# AltimeterFio_v3.net
KiCad netlist of a schematic drawn in EAGLE
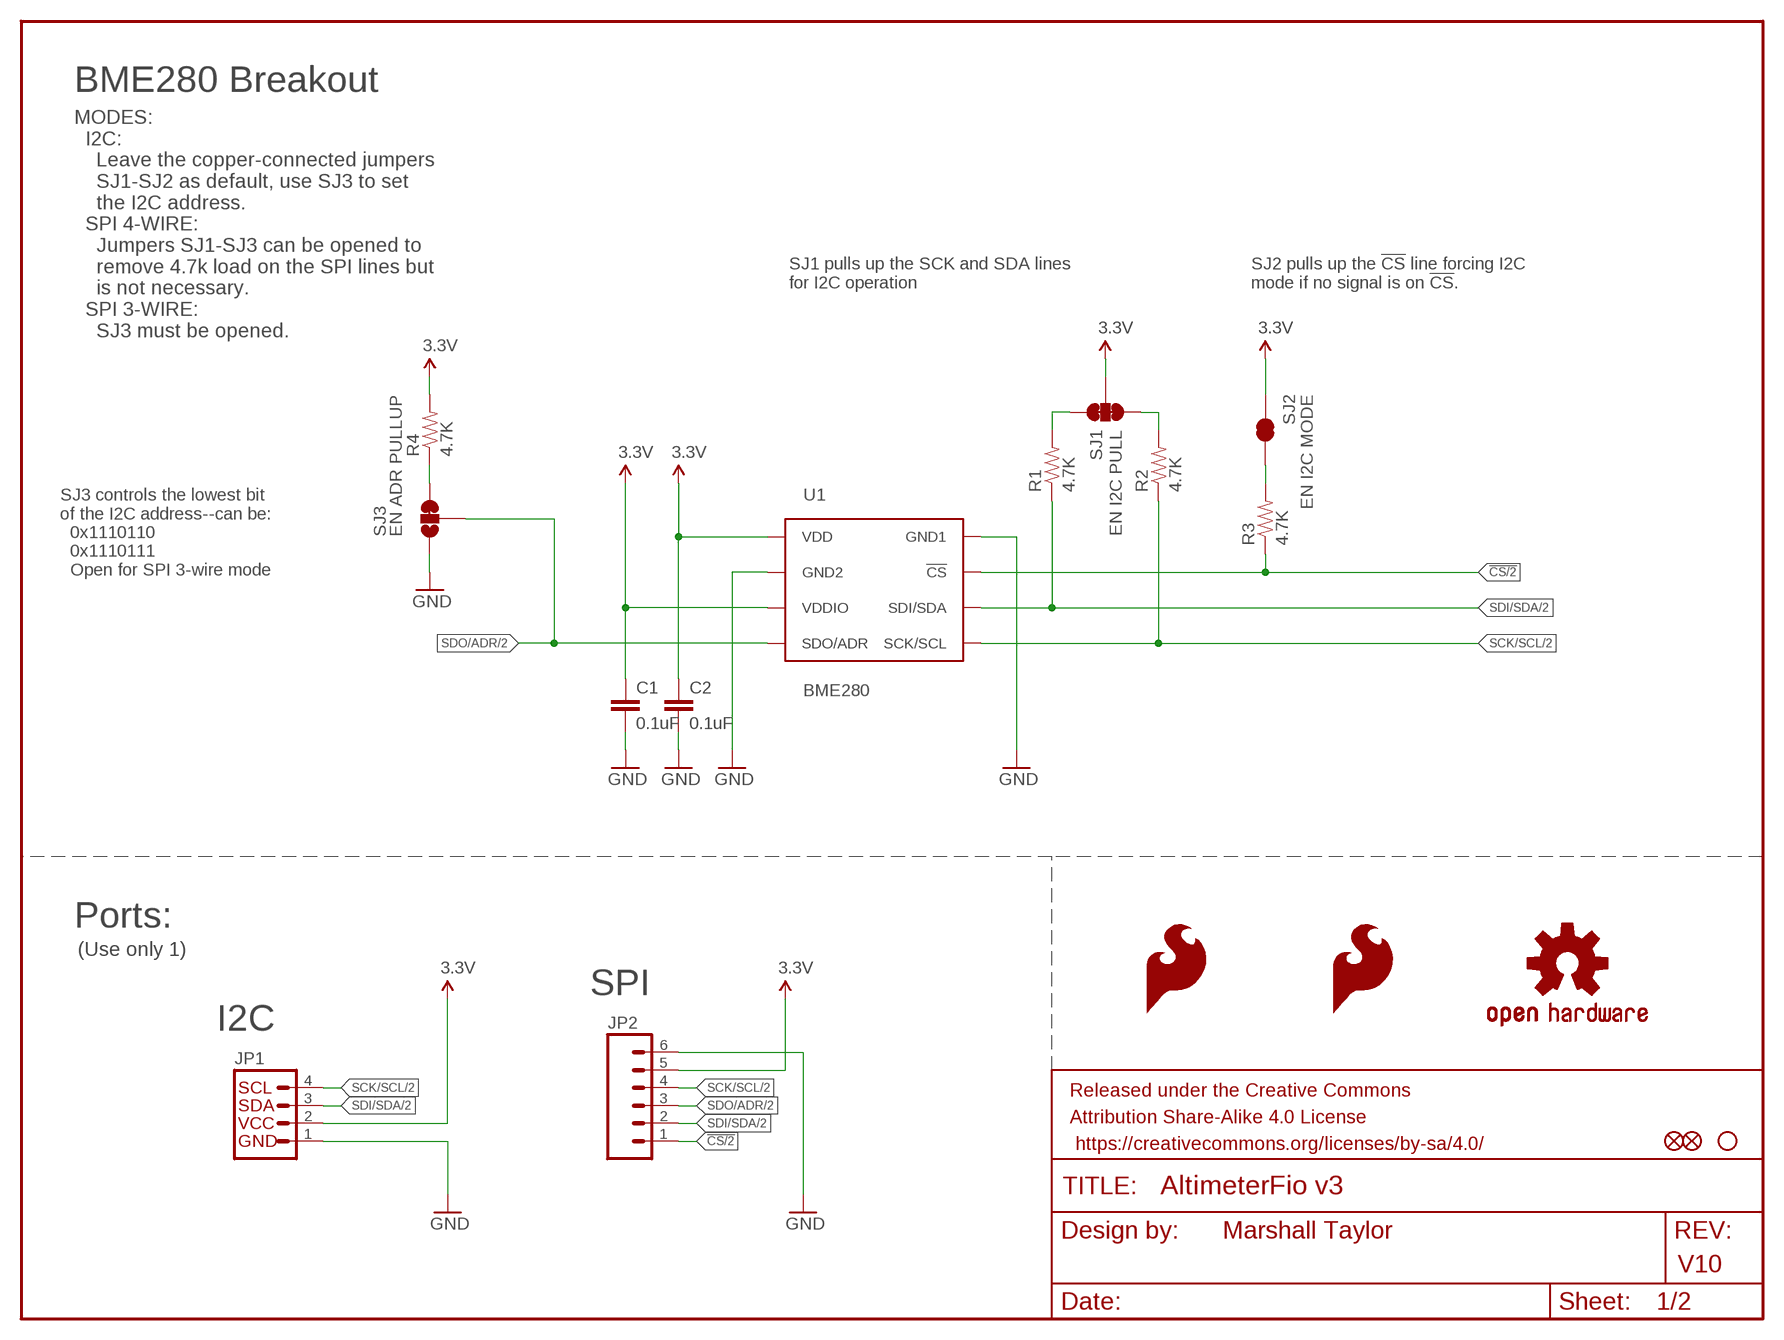
[diagram p0: schematic, sheet 1]
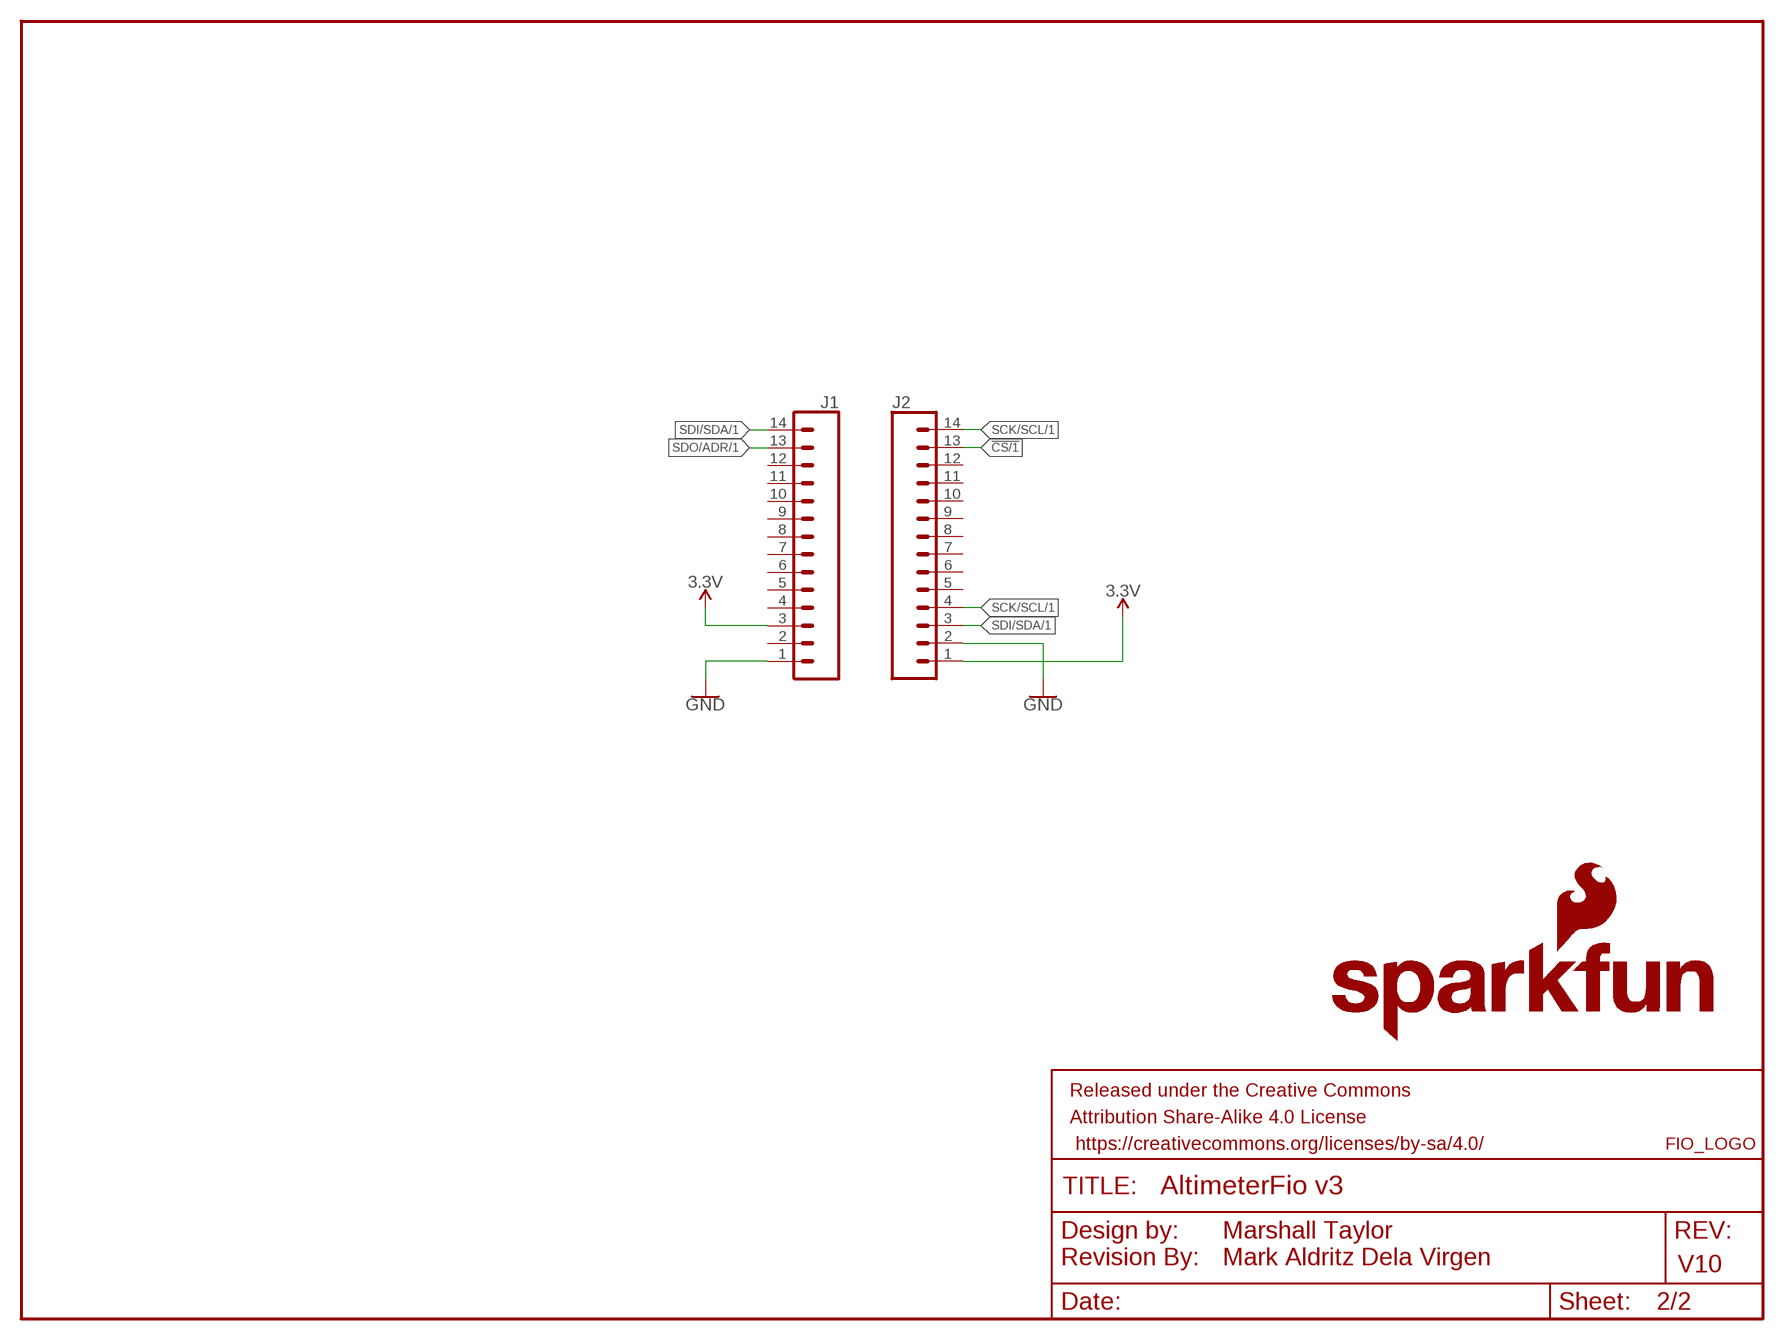
[diagram p1: schematic, sheet 2]

(export (version "E")
  (design (tool "Eeschema 10.0.6"))
  (components
    (comp (ref "FRAME2")
      (value "FRAME-LETTERNO_PACKAGE")
      (footprint "eagle-import:DUMMY")
      (fields (field (name "DESIGNER") "Nobody"))
      (libsource (lib "eagle-import") (part "SparkFun-Aesthetics_507_FRAME-LETTERNO_PACKAGE"))
    )
    (comp (ref "J1")
      (value "CONN_14")
      (footprint "eagle-import:1X14")
      (libsource (lib "eagle-import") (part "CONN_14"))
    )
    (comp (ref "J2")
      (value "CONN_14")
      (footprint "eagle-import:1X14")
      (libsource (lib "eagle-import") (part "CONN_14"))
    )
    (comp (ref "LOGO4")
      (value "FIO_LOGOV2")
      (footprint "eagle-import:FIO_LOGO")
      (libsource (lib "eagle-import") (part "FIO_LOGOV2"))
    )
    (comp (ref "LOGO5")
      (value "REVISION")
      (footprint "eagle-import:REVISION")
      (libsource (lib "eagle-import") (part "REVISION"))
    )
    (comp (ref "LOGO6")
      (value "SFE_LOGO_NAME_FLAME.1_INCH")
      (footprint "eagle-import:SFE_LOGO_NAME_FLAME_.1")
      (libsource (lib "eagle-import") (part "SFE_LOGO_NAME_FLAME.1_INCH"))
    )
    (comp (ref "C1")
      (value "0.1uF")
      (footprint "eagle-import:0603-CAP")
      (libsource (lib "eagle-import") (part "0.1UF-25V-5%(0603)"))
    )
    (comp (ref "C2")
      (value "0.1uF")
      (footprint "eagle-import:0603-CAP")
      (libsource (lib "eagle-import") (part "0.1UF-25V-5%(0603)"))
    )
    (comp (ref "FID1")
      (value "FIDUCIAL1X2")
      (footprint "eagle-import:FIDUCIAL-1X2")
      (libsource (lib "eagle-import") (part "FIDUCIAL1X2"))
    )
    (comp (ref "FID2")
      (value "FIDUCIAL1X2")
      (footprint "eagle-import:FIDUCIAL-1X2")
      (libsource (lib "eagle-import") (part "FIDUCIAL1X2"))
    )
    (comp (ref "FRAME1")
      (value "FRAME-LETTER")
      (footprint "eagle-import:CREATIVE_COMMONS")
      (libsource (lib "eagle-import") (part "FRAME-LETTER"))
    )
    (comp (ref "JP1")
      (value "I2C_STANDARD_NO_SILK")
      (footprint "eagle-import:1X04_NO_SILK")
      (libsource (lib "eagle-import") (part "I2C_STANDARD_NO_SILK"))
    )
    (comp (ref "JP2")
      (value "M06NO_SILK_FEMALE_PTH")
      (footprint "eagle-import:1X06_NO_SILK")
      (libsource (lib "eagle-import") (part "M06NO_SILK_FEMALE_PTH"))
    )
    (comp (ref "LOGO1")
      (value "SFE_LOGO_FLAME.1_INCH")
      (footprint "eagle-import:SFE_LOGO_FLAME_.1")
      (libsource (lib "eagle-import") (part "SFE_LOGO_FLAME.1_INCH"))
    )
    (comp (ref "LOGO2")
      (value "SFE_LOGO_FLAME.1_INCH")
      (footprint "eagle-import:SFE_LOGO_FLAME_.1")
      (libsource (lib "eagle-import") (part "SFE_LOGO_FLAME.1_INCH"))
    )
    (comp (ref "LOGO3")
      (value "OSHW-LOGOS")
      (footprint "eagle-import:OSHW-LOGO-S")
      (libsource (lib "eagle-import") (part "OSHW-LOGOS"))
    )
    (comp (ref "R1")
      (value "4.7K")
      (footprint "eagle-import:0603-RES")
      (libsource (lib "eagle-import") (part "4.7KOHM-1/10W-1%(0603)"))
    )
    (comp (ref "R2")
      (value "4.7K")
      (footprint "eagle-import:0603-RES")
      (libsource (lib "eagle-import") (part "4.7KOHM-1/10W-1%(0603)"))
    )
    (comp (ref "R3")
      (value "4.7K")
      (footprint "eagle-import:0603-RES")
      (libsource (lib "eagle-import") (part "4.7KOHM-1/10W-1%(0603)"))
    )
    (comp (ref "R4")
      (value "4.7K")
      (footprint "eagle-import:0603-RES")
      (libsource (lib "eagle-import") (part "4.7KOHM-1/10W-1%(0603)"))
    )
    (comp (ref "SJ1")
      (value "EN I2C PULL")
      (footprint "eagle-import:PAD-JUMPER-3-3OF3_NC_BY_TRACE_YES_SILK_FULL_BOX")
      (libsource (lib "eagle-import") (part "JUMPER-PAD-3-NC_BY_TRACE"))
    )
    (comp (ref "SJ2")
      (value "EN I2C MODE")
      (footprint "eagle-import:PAD-JUMPER-2-NC_BY_TRACE_YES_SILK")
      (libsource (lib "eagle-import") (part "JUMPER-PAD-2-NC_BY_TRACE"))
    )
    (comp (ref "SJ3")
      (value "EN ADR PULLUP")
      (footprint "eagle-import:PAD-JUMPER-3-2OF3_NC_BY_TRACE_YES_SILK_FULL_BOX")
      (libsource (lib "eagle-import") (part "JUMPER-PAD-3-2OF3_NC_BY_TRACE_SMALL"))
    )
    (comp (ref "STANDOFF4")
      (value "STAND-OFF")
      (footprint "eagle-import:STAND-OFF")
      (libsource (lib "eagle-import") (part "STAND-OFF"))
    )
    (comp (ref "U1")
      (value "BME280")
      (footprint "eagle-import:BME280_LGA")
      (libsource (lib "eagle-import") (part "BME280"))
    )
  )
  (nets
    (net (code "1") (name "3.3V") (class "Default")
      (node (ref "C1") (pin "1") (pinfunction "1_1") (pintype "passive"))
      (node (ref "C2") (pin "1") (pinfunction "1_1") (pintype "passive"))
      (node (ref "J1") (pin "3") (pinfunction "3_3") (pintype "passive"))
      (node (ref "J2") (pin "1") (pinfunction "1_1") (pintype "passive"))
      (node (ref "JP1") (pin "2") (pinfunction "2_2") (pintype "passive"))
      (node (ref "JP2") (pin "5") (pinfunction "5_5") (pintype "passive"))
      (node (ref "R4") (pin "2") (pinfunction "2_2") (pintype "passive"))
      (node (ref "SJ1") (pin "2") (pinfunction "2_2") (pintype "passive"))
      (node (ref "SJ2") (pin "2") (pinfunction "2_2") (pintype "passive"))
      (node (ref "U1") (pin "P$6") (pinfunction "VDDIO_P$6") (pintype "bidirectional"))
      (node (ref "U1") (pin "P$8") (pinfunction "VDD_P$8") (pintype "bidirectional"))
    )
    (net (code "2") (name "GND") (class "Default")
      (node (ref "C1") (pin "2") (pinfunction "2_2") (pintype "passive"))
      (node (ref "C2") (pin "2") (pinfunction "2_2") (pintype "passive"))
      (node (ref "J1") (pin "1") (pinfunction "1_1") (pintype "passive"))
      (node (ref "J2") (pin "2") (pinfunction "2_2") (pintype "passive"))
      (node (ref "JP1") (pin "1") (pinfunction "1_1") (pintype "passive"))
      (node (ref "JP2") (pin "6") (pinfunction "6_6") (pintype "passive"))
      (node (ref "SJ3") (pin "1") (pinfunction "1_1") (pintype "passive"))
      (node (ref "U1") (pin "P$1") (pinfunction "GND1_P$1") (pintype "bidirectional"))
      (node (ref "U1") (pin "P$7") (pinfunction "GND2_P$7") (pintype "bidirectional"))
    )
    (net (code "3") (name "Net-(R1-Pad2)") (class "Default")
      (node (ref "R1") (pin "2") (pinfunction "2_2") (pintype "passive"))
      (node (ref "SJ1") (pin "3") (pinfunction "3_3") (pintype "passive"))
    )
    (net (code "4") (name "Net-(R2-Pad2)") (class "Default")
      (node (ref "R2") (pin "2") (pinfunction "2_2") (pintype "passive"))
      (node (ref "SJ1") (pin "1") (pinfunction "1_1") (pintype "passive"))
    )
    (net (code "5") (name "Net-(R3-Pad2)") (class "Default")
      (node (ref "R3") (pin "2") (pinfunction "2_2") (pintype "passive"))
      (node (ref "SJ2") (pin "1") (pinfunction "1_1") (pintype "passive"))
    )
    (net (code "6") (name "Net-(R4-Pad1)") (class "Default")
      (node (ref "R4") (pin "1") (pinfunction "1_1") (pintype "passive"))
      (node (ref "SJ3") (pin "3") (pinfunction "3_3") (pintype "passive"))
    )
    (net (code "7") (name "SCK{slash}SCL") (class "Default")
      (node (ref "J2") (pin "14") (pinfunction "14_14") (pintype "passive"))
      (node (ref "J2") (pin "4") (pinfunction "4_4") (pintype "passive"))
      (node (ref "JP1") (pin "4") (pinfunction "4_4") (pintype "passive"))
      (node (ref "JP2") (pin "4") (pinfunction "4_4") (pintype "passive"))
      (node (ref "R2") (pin "1") (pinfunction "1_1") (pintype "passive"))
      (node (ref "U1") (pin "P$4") (pinfunction "SCK/SCL_P$4") (pintype "bidirectional"))
    )
    (net (code "8") (name "SDI{slash}SDA") (class "Default")
      (node (ref "J1") (pin "14") (pinfunction "14_14") (pintype "passive"))
      (node (ref "J2") (pin "3") (pinfunction "3_3") (pintype "passive"))
      (node (ref "JP1") (pin "3") (pinfunction "3_3") (pintype "passive"))
      (node (ref "JP2") (pin "2") (pinfunction "2_2") (pintype "passive"))
      (node (ref "R1") (pin "1") (pinfunction "1_1") (pintype "passive"))
      (node (ref "U1") (pin "P$3") (pinfunction "SDI/SDA_P$3") (pintype "bidirectional"))
    )
    (net (code "9") (name "SDO{slash}ADR") (class "Default")
      (node (ref "J1") (pin "13") (pinfunction "13_13") (pintype "passive"))
      (node (ref "JP2") (pin "3") (pinfunction "3_3") (pintype "passive"))
      (node (ref "SJ3") (pin "2") (pinfunction "2_2") (pintype "passive"))
      (node (ref "U1") (pin "P$5") (pinfunction "SDO/ADR_P$5") (pintype "bidirectional"))
    )
    (net (code "10") (name "unconnected-(J1-Pad2)") (class "Default")
      (node (ref "J1") (pin "2") (pinfunction "2_2") (pintype "passive"))
    )
    (net (code "11") (name "unconnected-(J1-Pad4)") (class "Default")
      (node (ref "J1") (pin "4") (pinfunction "4_4") (pintype "passive"))
    )
    (net (code "12") (name "unconnected-(J1-Pad5)") (class "Default")
      (node (ref "J1") (pin "5") (pinfunction "5_5") (pintype "passive"))
    )
    (net (code "13") (name "unconnected-(J1-Pad6)") (class "Default")
      (node (ref "J1") (pin "6") (pinfunction "6_6") (pintype "passive"))
    )
    (net (code "14") (name "unconnected-(J1-Pad7)") (class "Default")
      (node (ref "J1") (pin "7") (pinfunction "7_7") (pintype "passive"))
    )
    (net (code "15") (name "unconnected-(J1-Pad8)") (class "Default")
      (node (ref "J1") (pin "8") (pinfunction "8_8") (pintype "passive"))
    )
    (net (code "16") (name "unconnected-(J1-Pad9)") (class "Default")
      (node (ref "J1") (pin "9") (pinfunction "9_9") (pintype "passive"))
    )
    (net (code "17") (name "unconnected-(J1-Pad10)") (class "Default")
      (node (ref "J1") (pin "10") (pinfunction "10_10") (pintype "passive"))
    )
    (net (code "18") (name "unconnected-(J1-Pad11)") (class "Default")
      (node (ref "J1") (pin "11") (pinfunction "11_11") (pintype "passive"))
    )
    (net (code "19") (name "unconnected-(J1-Pad12)") (class "Default")
      (node (ref "J1") (pin "12") (pinfunction "12_12") (pintype "passive"))
    )
    (net (code "20") (name "unconnected-(J2-Pad5)") (class "Default")
      (node (ref "J2") (pin "5") (pinfunction "5_5") (pintype "passive"))
    )
    (net (code "21") (name "unconnected-(J2-Pad6)") (class "Default")
      (node (ref "J2") (pin "6") (pinfunction "6_6") (pintype "passive"))
    )
    (net (code "22") (name "unconnected-(J2-Pad7)") (class "Default")
      (node (ref "J2") (pin "7") (pinfunction "7_7") (pintype "passive"))
    )
    (net (code "23") (name "unconnected-(J2-Pad8)") (class "Default")
      (node (ref "J2") (pin "8") (pinfunction "8_8") (pintype "passive"))
    )
    (net (code "24") (name "unconnected-(J2-Pad9)") (class "Default")
      (node (ref "J2") (pin "9") (pinfunction "9_9") (pintype "passive"))
    )
    (net (code "25") (name "unconnected-(J2-Pad10)") (class "Default")
      (node (ref "J2") (pin "10") (pinfunction "10_10") (pintype "passive"))
    )
    (net (code "26") (name "unconnected-(J2-Pad11)") (class "Default")
      (node (ref "J2") (pin "11") (pinfunction "11_11") (pintype "passive"))
    )
    (net (code "27") (name "unconnected-(J2-Pad12)") (class "Default")
      (node (ref "J2") (pin "12") (pinfunction "12_12") (pintype "passive"))
    )
    (net (code "28") (name "~{CS}") (class "Default")
      (node (ref "J2") (pin "13") (pinfunction "13_13") (pintype "passive"))
      (node (ref "JP2") (pin "1") (pinfunction "1_1") (pintype "passive"))
      (node (ref "R3") (pin "1") (pinfunction "1_1") (pintype "passive"))
      (node (ref "U1") (pin "P$2") (pinfunction "~{CS}_P$2") (pintype "bidirectional"))
    )
  )
)
